# RPICM4.net
KiCad netlist of a schematic drawn in Altium Designer
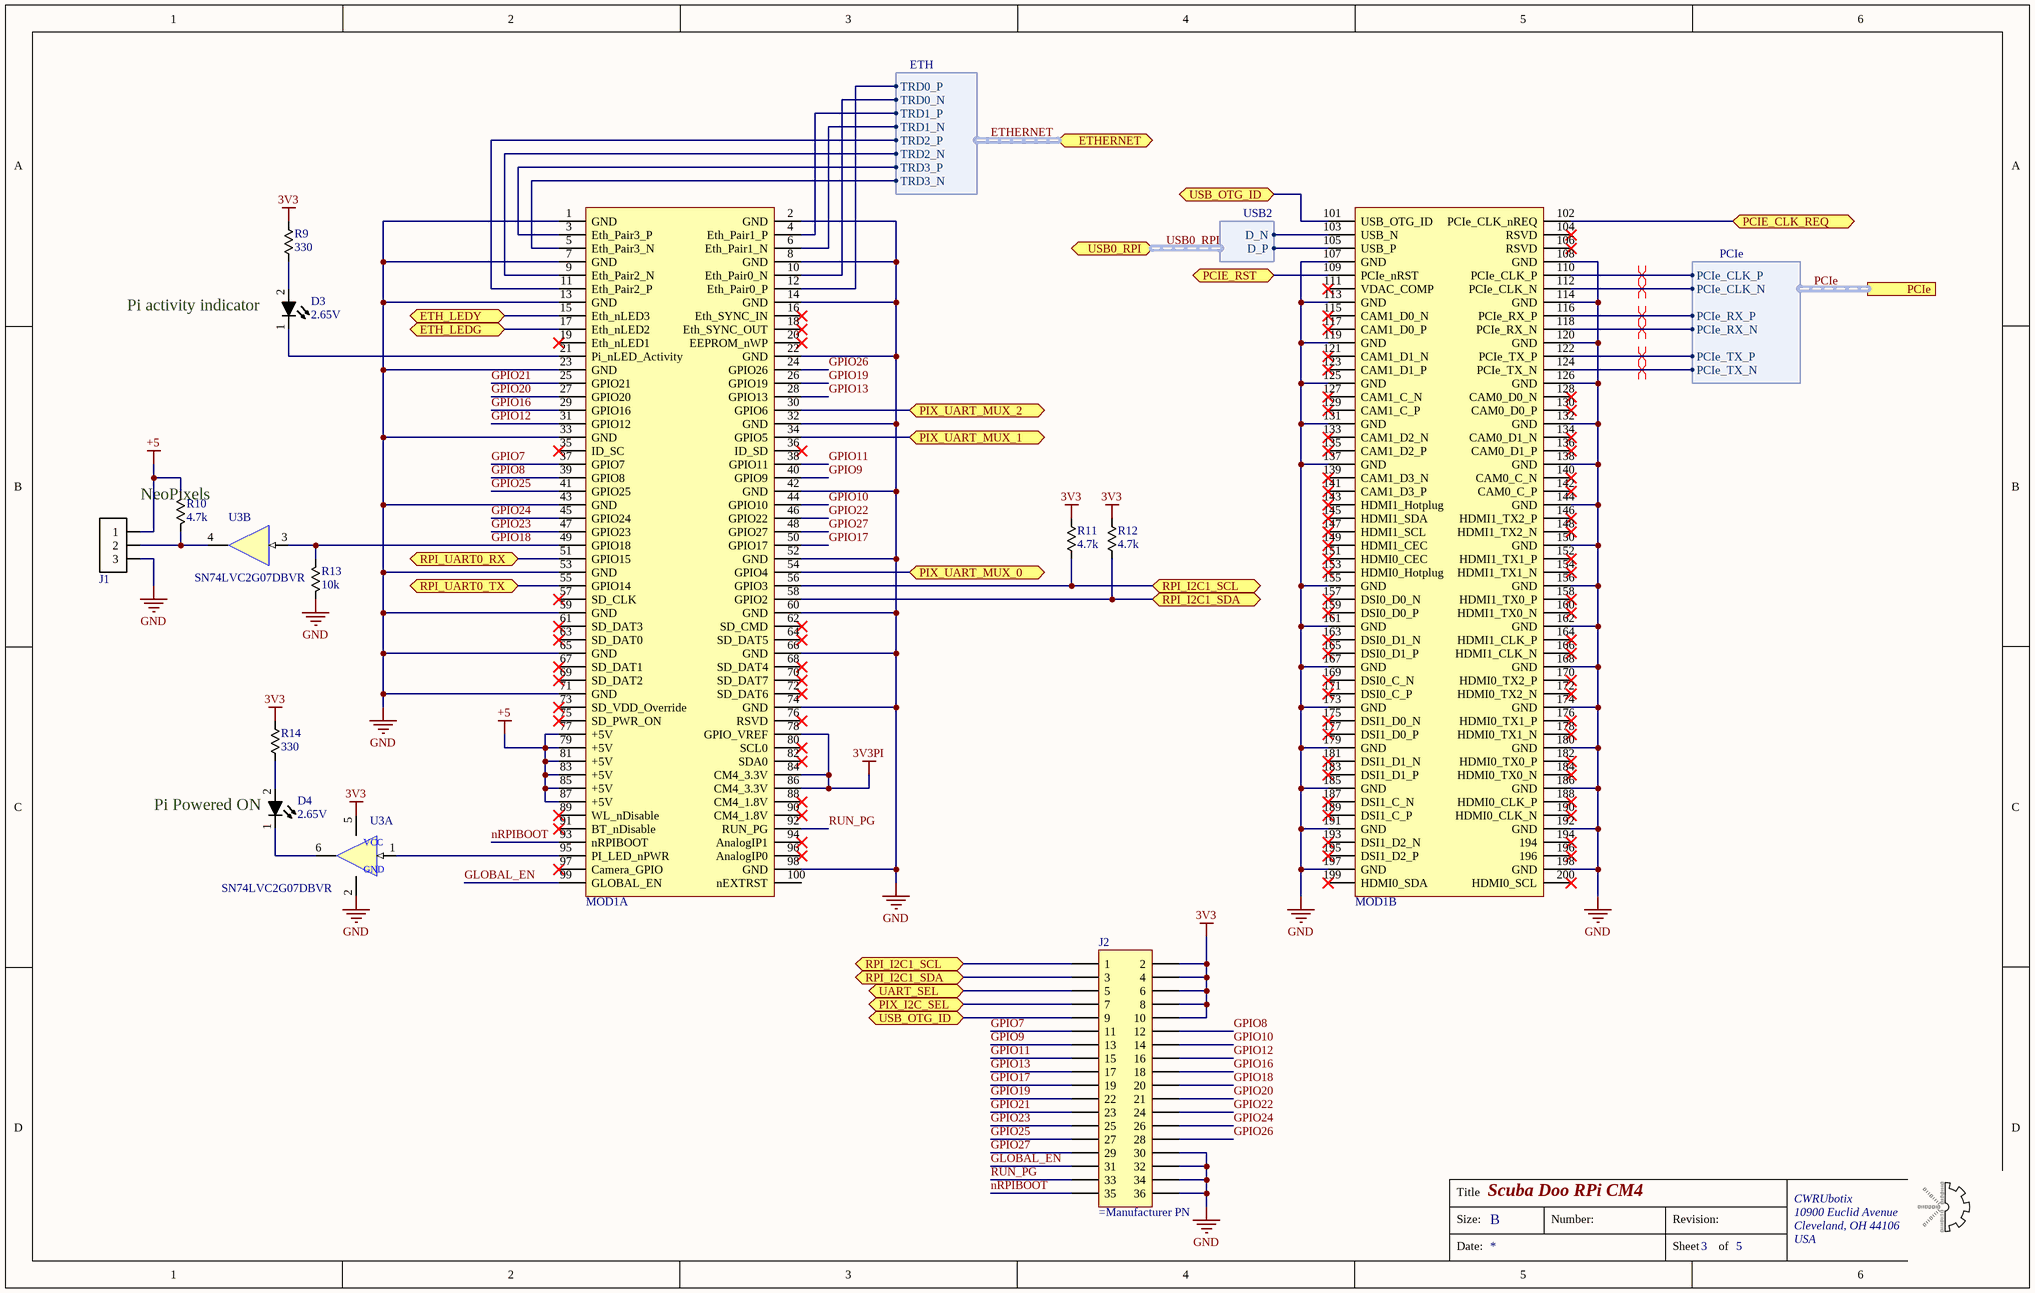
[diagram p0: RPICM4.SchDoc]

(export (version "E")
  (design (tool "Eeschema 10.0.6"))
  (components
    (comp (ref "D3")
      (value "2.65V")
      (footprint "chip_0603_LED")
      (description "LED, Green, 0603, Low current, HELI2 Series")
      (fields (field (name "PART NUMBER") "DIO-00050") (field (name "MANUFACTURER") "Kingbright"))
      (libsource (lib "Diodes$") (part "DIO-00050"))
    )
    (comp (ref "D4")
      (value "2.65V")
      (footprint "chip_0603_LED")
      (description "LED, Green, 0603, Low current, HELI2 Series")
      (fields (field (name "PART NUMBER") "DIO-00050") (field (name "MANUFACTURER") "Kingbright"))
      (libsource (lib "Diodes$") (part "DIO-00050"))
    )
    (comp (ref "J1")
      (value "conn-3x1_0")
      (footprint "HDDR_3x1_0")
      (description "Header, 3x1, 0.1\"")
      (fields (field (name "PART NUMBER") "CONN-00037"))
      (libsource (lib "Connectors$") (part "CONN-00037"))
    )
    (comp (ref "J2")
      (value "~")
      (footprint "HDDR_18X2_0")
      (description "Header 18x2, 0.1\"")
      (fields (field (name "PART NUMBER") "CONN-00005"))
      (libsource (lib "Connectors$") (part "CONN-00005"))
    )
    (comp (ref "MOD1")
      (value "CM4004032")
      (footprint "RPI_CM4_3MM")
      (description "Raspberry Pi 4 Compute Module, CM4, 4GB DDR4, 32 GB eMMC")
      (fields
        (field (name "PART NUMBER") "MISC-00060")
        (field (name "MANUFACTURER") "Raspberry Pi Foundation")
      )
      (libsource (lib "Misc$") (part "MISC-00060"))
    )
    (comp (ref "R9")
      (value "330")
      (footprint "chip_0603")
      (description "RES SMD 330 OHM 1% 1/4W 0603")
      (fields (field (name "PART NUMBER") "RES-00221") (field (name "TOLERANCE") "1%"))
      (libsource (lib "Resistors$") (part "RES-00221"))
    )
    (comp (ref "R10")
      (value "4.7k")
      (footprint "chip_0603")
      (description "RES SMD 4.7K OHM 1% 1/4W 0603")
      (fields (field (name "PART NUMBER") "RES-00470") (field (name "TOLERANCE") "1%"))
      (libsource (lib "Resistors$") (part "RES-00470"))
    )
    (comp (ref "R11")
      (value "4.7k")
      (footprint "chip_0603")
      (description "RES SMD 4.7K OHM 1% 1/4W 0603")
      (fields (field (name "PART NUMBER") "RES-00470") (field (name "TOLERANCE") "1%"))
      (libsource (lib "Resistors$") (part "RES-00470"))
    )
    (comp (ref "R12")
      (value "4.7k")
      (footprint "chip_0603")
      (description "RES SMD 4.7K OHM 1% 1/4W 0603")
      (fields (field (name "PART NUMBER") "RES-00470") (field (name "TOLERANCE") "1%"))
      (libsource (lib "Resistors$") (part "RES-00470"))
    )
    (comp (ref "R13")
      (value "10k")
      (footprint "chip_0603")
      (description "RES SMD 10K OHM 1% 1/4W 0603")
      (fields (field (name "PART NUMBER") "RES-00306") (field (name "TOLERANCE") "1%"))
      (libsource (lib "Resistors$") (part "RES-00306"))
    )
    (comp (ref "R14")
      (value "330")
      (footprint "chip_0603")
      (description "RES SMD 330 OHM 1% 1/4W 0603")
      (fields (field (name "PART NUMBER") "RES-00221") (field (name "TOLERANCE") "1%"))
      (libsource (lib "Resistors$") (part "RES-00221"))
    )
    (comp (ref "U3")
      (value "SN74LVC2G07DBVR")
      (footprint "sot-23-6")
      (description "IC, Buffer Non-Inverting, Dual, Open-Drain Outputs, 1.65~5.5V, SOT-23-6")
      (fields (field (name "PART NUMBER") "LOGIC-00046") (field (name "MANUFACTURER") "TI"))
      (libsource (lib "Logic$") (part "LOGIC-00046"))
    )
  )
  (nets
    (net (code "4") (name "+5") (class "Default")
      (node (ref "J1") (pin "1") (pinfunction "1_1") (pintype "passive"))
      (node (ref "MOD1") (pin "77") (pinfunction "+5V_77") (pintype "passive"))
      (node (ref "MOD1") (pin "79") (pinfunction "+5V_79") (pintype "passive"))
      (node (ref "MOD1") (pin "81") (pinfunction "+5V_81") (pintype "passive"))
      (node (ref "MOD1") (pin "83") (pinfunction "+5V_83") (pintype "passive"))
      (node (ref "MOD1") (pin "85") (pinfunction "+5V_85") (pintype "passive"))
      (node (ref "MOD1") (pin "87") (pinfunction "+5V_87") (pintype "passive"))
      (node (ref "R10") (pin "1") (pinfunction "1_1") (pintype "passive"))
    )
    (net (code "5") (name "/D_N") (class "Default")
      (node (ref "MOD1") (pin "103") (pinfunction "USB_N_103") (pintype "passive"))
    )
    (net (code "6") (name "/D_P") (class "Default")
      (node (ref "MOD1") (pin "105") (pinfunction "USB_P_105") (pintype "passive"))
    )
    (net (code "8") (name "/ETH_LEDG") (class "Default")
      (node (ref "MOD1") (pin "17") (pinfunction "Eth_nLED2_17") (pintype "passive"))
    )
    (net (code "9") (name "/ETH_LEDY") (class "Default")
      (node (ref "MOD1") (pin "15") (pinfunction "Eth_nLED3_15") (pintype "passive"))
    )
    (net (code "10") (name "/GLOBAL_EN") (class "Default")
      (node (ref "J2") (pin "31") (pinfunction "31_31") (pintype "passive"))
      (node (ref "MOD1") (pin "99") (pinfunction "GLOBAL_EN_99") (pintype "passive"))
    )
    (net (code "11") (name "/GPIO7") (class "Default")
      (node (ref "J2") (pin "11") (pinfunction "11_11") (pintype "passive"))
      (node (ref "MOD1") (pin "37") (pinfunction "GPIO7_37") (pintype "passive"))
    )
    (net (code "12") (name "/GPIO8") (class "Default")
      (node (ref "J2") (pin "12") (pinfunction "12_12") (pintype "passive"))
      (node (ref "MOD1") (pin "39") (pinfunction "GPIO8_39") (pintype "passive"))
    )
    (net (code "13") (name "/GPIO9") (class "Default")
      (node (ref "J2") (pin "13") (pinfunction "13_13") (pintype "passive"))
      (node (ref "MOD1") (pin "40") (pinfunction "GPIO9_40") (pintype "passive"))
    )
    (net (code "14") (name "/GPIO10") (class "Default")
      (node (ref "J2") (pin "14") (pinfunction "14_14") (pintype "passive"))
      (node (ref "MOD1") (pin "44") (pinfunction "GPIO10_44") (pintype "passive"))
    )
    (net (code "15") (name "/GPIO11") (class "Default")
      (node (ref "J2") (pin "15") (pinfunction "15_15") (pintype "passive"))
      (node (ref "MOD1") (pin "38") (pinfunction "GPIO11_38") (pintype "passive"))
    )
    (net (code "16") (name "/GPIO12") (class "Default")
      (node (ref "J2") (pin "16") (pinfunction "16_16") (pintype "passive"))
      (node (ref "MOD1") (pin "31") (pinfunction "GPIO12_31") (pintype "passive"))
    )
    (net (code "17") (name "/GPIO13") (class "Default")
      (node (ref "J2") (pin "17") (pinfunction "17_17") (pintype "passive"))
      (node (ref "MOD1") (pin "28") (pinfunction "GPIO13_28") (pintype "passive"))
    )
    (net (code "18") (name "/GPIO16") (class "Default")
      (node (ref "J2") (pin "18") (pinfunction "18_18") (pintype "passive"))
      (node (ref "MOD1") (pin "29") (pinfunction "GPIO16_29") (pintype "passive"))
    )
    (net (code "19") (name "/GPIO17") (class "Default")
      (node (ref "J2") (pin "19") (pinfunction "19_19") (pintype "passive"))
      (node (ref "MOD1") (pin "50") (pinfunction "GPIO17_50") (pintype "passive"))
    )
    (net (code "20") (name "/GPIO18") (class "Default")
      (node (ref "J2") (pin "20") (pinfunction "20_20") (pintype "passive"))
      (node (ref "MOD1") (pin "49") (pinfunction "GPIO18_49") (pintype "passive"))
      (node (ref "R13") (pin "1") (pinfunction "1_1") (pintype "passive"))
      (node (ref "U3") (pin "3") (pinfunction "2A_3") (pintype "input"))
    )
    (net (code "21") (name "/GPIO19") (class "Default")
      (node (ref "J2") (pin "22") (pinfunction "22_22") (pintype "passive"))
      (node (ref "MOD1") (pin "26") (pinfunction "GPIO19_26") (pintype "passive"))
    )
    (net (code "22") (name "/GPIO20") (class "Default")
      (node (ref "J2") (pin "21") (pinfunction "21_21") (pintype "passive"))
      (node (ref "MOD1") (pin "27") (pinfunction "GPIO20_27") (pintype "passive"))
    )
    (net (code "23") (name "/GPIO21") (class "Default")
      (node (ref "J2") (pin "23") (pinfunction "23_23") (pintype "passive"))
      (node (ref "MOD1") (pin "25") (pinfunction "GPIO21_25") (pintype "passive"))
    )
    (net (code "24") (name "/GPIO22") (class "Default")
      (node (ref "J2") (pin "24") (pinfunction "24_24") (pintype "passive"))
      (node (ref "MOD1") (pin "46") (pinfunction "GPIO22_46") (pintype "passive"))
    )
    (net (code "25") (name "/GPIO23") (class "Default")
      (node (ref "J2") (pin "25") (pinfunction "25_25") (pintype "passive"))
      (node (ref "MOD1") (pin "47") (pinfunction "GPIO23_47") (pintype "passive"))
    )
    (net (code "26") (name "/GPIO24") (class "Default")
      (node (ref "J2") (pin "26") (pinfunction "26_26") (pintype "passive"))
      (node (ref "MOD1") (pin "45") (pinfunction "GPIO24_45") (pintype "passive"))
    )
    (net (code "27") (name "/GPIO25") (class "Default")
      (node (ref "J2") (pin "27") (pinfunction "27_27") (pintype "passive"))
      (node (ref "MOD1") (pin "41") (pinfunction "GPIO25_41") (pintype "passive"))
    )
    (net (code "28") (name "/GPIO26") (class "Default")
      (node (ref "J2") (pin "28") (pinfunction "28_28") (pintype "passive"))
      (node (ref "MOD1") (pin "24") (pinfunction "GPIO26_24") (pintype "passive"))
    )
    (net (code "29") (name "/GPIO27") (class "Default")
      (node (ref "J2") (pin "29") (pinfunction "29_29") (pintype "passive"))
      (node (ref "MOD1") (pin "48") (pinfunction "GPIO27_48") (pintype "passive"))
    )
    (net (code "30") (name "/PCIE_CLK_REQ") (class "Default")
      (node (ref "MOD1") (pin "102") (pinfunction "PCIe_CLK_nREQ_102") (pintype "passive"))
    )
    (net (code "31") (name "/PCIE_RST") (class "Default")
      (node (ref "MOD1") (pin "109") (pinfunction "PCIe_nRST_109") (pintype "passive"))
    )
    (net (code "32") (name "/PCIe_CLK_N") (class "Default")
      (node (ref "MOD1") (pin "112") (pinfunction "PCIe_CLK_N_112") (pintype "passive"))
    )
    (net (code "33") (name "/PCIe_CLK_P") (class "Default")
      (node (ref "MOD1") (pin "110") (pinfunction "PCIe_CLK_P_110") (pintype "passive"))
    )
    (net (code "34") (name "/PCIe_RX_N") (class "Default")
      (node (ref "MOD1") (pin "118") (pinfunction "PCIe_RX_N_118") (pintype "passive"))
    )
    (net (code "35") (name "/PCIe_RX_P") (class "Default")
      (node (ref "MOD1") (pin "116") (pinfunction "PCIe_RX_P_116") (pintype "passive"))
    )
    (net (code "36") (name "/PCIe_TX_N") (class "Default")
      (node (ref "MOD1") (pin "124") (pinfunction "PCIe_TX_N_124") (pintype "passive"))
    )
    (net (code "37") (name "/PCIe_TX_P") (class "Default")
      (node (ref "MOD1") (pin "122") (pinfunction "PCIe_TX_P_122") (pintype "passive"))
    )
    (net (code "39") (name "/PIX_I2C_SEL") (class "Default")
      (node (ref "J2") (pin "7") (pinfunction "7_7") (pintype "passive"))
    )
    (net (code "40") (name "/PIX_UART_MUX_0") (class "Default")
      (node (ref "MOD1") (pin "54") (pinfunction "GPIO4_54") (pintype "passive"))
    )
    (net (code "41") (name "/PIX_UART_MUX_1") (class "Default")
      (node (ref "MOD1") (pin "34") (pinfunction "GPIO5_34") (pintype "passive"))
    )
    (net (code "42") (name "/PIX_UART_MUX_2") (class "Default")
      (node (ref "MOD1") (pin "30") (pinfunction "GPIO6_30") (pintype "passive"))
    )
    (net (code "43") (name "/RPI_I2C1_SCL") (class "Default")
      (node (ref "J2") (pin "1") (pinfunction "1_1") (pintype "passive"))
      (node (ref "MOD1") (pin "56") (pinfunction "GPIO3_56") (pintype "passive"))
      (node (ref "R11") (pin "2") (pinfunction "2_2") (pintype "passive"))
    )
    (net (code "44") (name "/RPI_I2C1_SDA") (class "Default")
      (node (ref "J2") (pin "3") (pinfunction "3_3") (pintype "passive"))
      (node (ref "MOD1") (pin "58") (pinfunction "GPIO2_58") (pintype "passive"))
      (node (ref "R12") (pin "2") (pinfunction "2_2") (pintype "passive"))
    )
    (net (code "45") (name "/RPI_UART0_RX") (class "Default")
      (node (ref "MOD1") (pin "51") (pinfunction "GPIO15_51") (pintype "passive"))
    )
    (net (code "46") (name "/RPI_UART0_TX") (class "Default")
      (node (ref "MOD1") (pin "55") (pinfunction "GPIO14_55") (pintype "passive"))
    )
    (net (code "47") (name "/RUN_PG") (class "Default")
      (node (ref "J2") (pin "33") (pinfunction "33_33") (pintype "passive"))
      (node (ref "MOD1") (pin "92") (pinfunction "RUN_PG_92") (pintype "passive"))
    )
    (net (code "48") (name "/TRD0_N") (class "Default")
      (node (ref "MOD1") (pin "10") (pinfunction "Eth_Pair0_N_10") (pintype "passive"))
    )
    (net (code "49") (name "/TRD0_P") (class "Default")
      (node (ref "MOD1") (pin "12") (pinfunction "Eth_Pair0_P_12") (pintype "passive"))
    )
    (net (code "50") (name "/TRD1_N") (class "Default")
      (node (ref "MOD1") (pin "6") (pinfunction "Eth_Pair1_N_6") (pintype "passive"))
    )
    (net (code "51") (name "/TRD1_P") (class "Default")
      (node (ref "MOD1") (pin "4") (pinfunction "Eth_Pair1_P_4") (pintype "passive"))
    )
    (net (code "52") (name "/TRD2_N") (class "Default")
      (node (ref "MOD1") (pin "9") (pinfunction "Eth_Pair2_N_9") (pintype "passive"))
    )
    (net (code "53") (name "/TRD2_P") (class "Default")
      (node (ref "MOD1") (pin "11") (pinfunction "Eth_Pair2_P_11") (pintype "passive"))
    )
    (net (code "54") (name "/TRD3_N") (class "Default")
      (node (ref "MOD1") (pin "5") (pinfunction "Eth_Pair3_N_5") (pintype "passive"))
    )
    (net (code "55") (name "/TRD3_P") (class "Default")
      (node (ref "MOD1") (pin "3") (pinfunction "Eth_Pair3_P_3") (pintype "passive"))
    )
    (net (code "56") (name "/UART_SEL") (class "Default")
      (node (ref "J2") (pin "5") (pinfunction "5_5") (pintype "passive"))
    )
    (net (code "58") (name "/USB_OTG_ID") (class "Default")
      (node (ref "J2") (pin "9") (pinfunction "9_9") (pintype "passive"))
      (node (ref "MOD1") (pin "101") (pinfunction "USB_OTG_ID_101") (pintype "passive"))
    )
    (net (code "59") (name "/nRPIBOOT") (class "Default")
      (node (ref "J2") (pin "35") (pinfunction "35_35") (pintype "passive"))
      (node (ref "MOD1") (pin "93") (pinfunction "nRPIBOOT_93") (pintype "passive"))
    )
    (net (code "60") (name "3V3") (class "Default")
      (node (ref "J2") (pin "10") (pinfunction "10_10") (pintype "passive"))
      (node (ref "J2") (pin "2") (pinfunction "2_2") (pintype "passive"))
      (node (ref "J2") (pin "4") (pinfunction "4_4") (pintype "passive"))
      (node (ref "J2") (pin "6") (pinfunction "6_6") (pintype "passive"))
      (node (ref "J2") (pin "8") (pinfunction "8_8") (pintype "passive"))
      (node (ref "R11") (pin "1") (pinfunction "1_1") (pintype "passive"))
      (node (ref "R12") (pin "1") (pinfunction "1_1") (pintype "passive"))
      (node (ref "R14") (pin "1") (pinfunction "1_1") (pintype "passive"))
      (node (ref "R9") (pin "1") (pinfunction "1_1") (pintype "passive"))
      (node (ref "U3") (pin "5") (pinfunction "VCC_5") (pintype "power_in"))
    )
    (net (code "61") (name "3V3PI") (class "Default")
      (node (ref "MOD1") (pin "78") (pinfunction "GPIO_VREF_78") (pintype "passive"))
      (node (ref "MOD1") (pin "84") (pinfunction "CM4_3.3V_84") (pintype "passive"))
      (node (ref "MOD1") (pin "86") (pinfunction "CM4_3.3V_86") (pintype "passive"))
    )
    (net (code "62") (name "GND") (class "Default")
      (node (ref "J1") (pin "3") (pinfunction "3_3") (pintype "passive"))
      (node (ref "J2") (pin "30") (pinfunction "30_30") (pintype "passive"))
      (node (ref "J2") (pin "32") (pinfunction "32_32") (pintype "passive"))
      (node (ref "J2") (pin "34") (pinfunction "34_34") (pintype "passive"))
      (node (ref "J2") (pin "36") (pinfunction "36_36") (pintype "passive"))
      (node (ref "MOD1") (pin "1") (pinfunction "GND_1") (pintype "passive"))
      (node (ref "MOD1") (pin "107") (pinfunction "GND_107") (pintype "passive"))
      (node (ref "MOD1") (pin "108") (pinfunction "GND_108") (pintype "passive"))
      (node (ref "MOD1") (pin "113") (pinfunction "GND_113") (pintype "passive"))
      (node (ref "MOD1") (pin "114") (pinfunction "GND_114") (pintype "passive"))
      (node (ref "MOD1") (pin "119") (pinfunction "GND_119") (pintype "passive"))
      (node (ref "MOD1") (pin "120") (pinfunction "GND_120") (pintype "passive"))
      (node (ref "MOD1") (pin "125") (pinfunction "GND_125") (pintype "passive"))
      (node (ref "MOD1") (pin "126") (pinfunction "GND_126") (pintype "passive"))
      (node (ref "MOD1") (pin "13") (pinfunction "GND_13") (pintype "passive"))
      (node (ref "MOD1") (pin "131") (pinfunction "GND_131") (pintype "passive"))
      (node (ref "MOD1") (pin "132") (pinfunction "GND_132") (pintype "passive"))
      (node (ref "MOD1") (pin "137") (pinfunction "GND_137") (pintype "passive"))
      (node (ref "MOD1") (pin "138") (pinfunction "GND_138") (pintype "passive"))
      (node (ref "MOD1") (pin "14") (pinfunction "GND_14") (pintype "passive"))
      (node (ref "MOD1") (pin "144") (pinfunction "GND_144") (pintype "passive"))
      (node (ref "MOD1") (pin "150") (pinfunction "GND_150") (pintype "passive"))
      (node (ref "MOD1") (pin "155") (pinfunction "GND_155") (pintype "passive"))
      (node (ref "MOD1") (pin "156") (pinfunction "GND_156") (pintype "passive"))
      (node (ref "MOD1") (pin "161") (pinfunction "GND_161") (pintype "passive"))
      (node (ref "MOD1") (pin "162") (pinfunction "GND_162") (pintype "passive"))
      (node (ref "MOD1") (pin "167") (pinfunction "GND_167") (pintype "passive"))
      (node (ref "MOD1") (pin "168") (pinfunction "GND_168") (pintype "passive"))
      (node (ref "MOD1") (pin "173") (pinfunction "GND_173") (pintype "passive"))
      (node (ref "MOD1") (pin "174") (pinfunction "GND_174") (pintype "passive"))
      (node (ref "MOD1") (pin "179") (pinfunction "GND_179") (pintype "passive"))
      (node (ref "MOD1") (pin "180") (pinfunction "GND_180") (pintype "passive"))
      (node (ref "MOD1") (pin "185") (pinfunction "GND_185") (pintype "passive"))
      (node (ref "MOD1") (pin "186") (pinfunction "GND_186") (pintype "passive"))
      (node (ref "MOD1") (pin "191") (pinfunction "GND_191") (pintype "passive"))
      (node (ref "MOD1") (pin "192") (pinfunction "GND_192") (pintype "passive"))
      (node (ref "MOD1") (pin "197") (pinfunction "GND_197") (pintype "passive"))
      (node (ref "MOD1") (pin "198") (pinfunction "GND_198") (pintype "passive"))
      (node (ref "MOD1") (pin "2") (pinfunction "GND_2") (pintype "passive"))
      (node (ref "MOD1") (pin "22") (pinfunction "GND_22") (pintype "passive"))
      (node (ref "MOD1") (pin "23") (pinfunction "GND_23") (pintype "passive"))
      (node (ref "MOD1") (pin "32") (pinfunction "GND_32") (pintype "passive"))
      (node (ref "MOD1") (pin "33") (pinfunction "GND_33") (pintype "passive"))
      (node (ref "MOD1") (pin "42") (pinfunction "GND_42") (pintype "passive"))
      (node (ref "MOD1") (pin "43") (pinfunction "GND_43") (pintype "passive"))
      (node (ref "MOD1") (pin "52") (pinfunction "GND_52") (pintype "passive"))
      (node (ref "MOD1") (pin "53") (pinfunction "GND_53") (pintype "passive"))
      (node (ref "MOD1") (pin "59") (pinfunction "GND_59") (pintype "passive"))
      (node (ref "MOD1") (pin "60") (pinfunction "GND_60") (pintype "passive"))
      (node (ref "MOD1") (pin "65") (pinfunction "GND_65") (pintype "passive"))
      (node (ref "MOD1") (pin "66") (pinfunction "GND_66") (pintype "passive"))
      (node (ref "MOD1") (pin "7") (pinfunction "GND_7") (pintype "passive"))
      (node (ref "MOD1") (pin "71") (pinfunction "GND_71") (pintype "passive"))
      (node (ref "MOD1") (pin "74") (pinfunction "GND_74") (pintype "passive"))
      (node (ref "MOD1") (pin "8") (pinfunction "GND_8") (pintype "passive"))
      (node (ref "MOD1") (pin "98") (pinfunction "GND_98") (pintype "passive"))
      (node (ref "R13") (pin "2") (pinfunction "2_2") (pintype "passive"))
      (node (ref "U3") (pin "2") (pinfunction "GND_2") (pintype "power_in"))
    )
    (net (code "63") (name "Net-(D3-Pad2)") (class "Default")
      (node (ref "D3") (pin "2") (pinfunction "2_2") (pintype "passive"))
      (node (ref "R9") (pin "2") (pinfunction "2_2") (pintype "passive"))
    )
    (net (code "64") (name "Net-(D4-Pad2)") (class "Default")
      (node (ref "D4") (pin "2") (pinfunction "2_2") (pintype "passive"))
      (node (ref "R14") (pin "2") (pinfunction "2_2") (pintype "passive"))
    )
    (net (code "65") (name "Net-(MOD1A-PI_LED_nPWR)") (class "Default")
      (node (ref "MOD1") (pin "95") (pinfunction "PI_LED_nPWR_95") (pintype "passive"))
      (node (ref "U3") (pin "1") (pinfunction "1A_1") (pintype "input"))
    )
    (net (code "66") (name "Net-(MOD1A-Pi_nLED_Activity)") (class "Default")
      (node (ref "D3") (pin "1") (pinfunction "1_1") (pintype "passive"))
      (node (ref "MOD1") (pin "21") (pinfunction "Pi_nLED_Activity_21") (pintype "passive"))
    )
    (net (code "67") (name "Net-(U3A-1Y)") (class "Default")
      (node (ref "D4") (pin "1") (pinfunction "1_1") (pintype "passive"))
      (node (ref "U3") (pin "6") (pinfunction "1Y_6") (pintype "open_collector"))
    )
    (net (code "68") (name "Net-(U3B-2Y)") (class "Default")
      (node (ref "J1") (pin "2") (pinfunction "2_2") (pintype "passive"))
      (node (ref "R10") (pin "2") (pinfunction "2_2") (pintype "passive"))
      (node (ref "U3") (pin "4") (pinfunction "2Y_4") (pintype "open_collector"))
    )
    (net (code "69") (name "unconnected-(MOD1-Pad194)") (class "Default")
      (node (ref "MOD1") (pin "194") (pinfunction "194_194") (pintype "passive+no_connect"))
    )
    (net (code "70") (name "unconnected-(MOD1-Pad196)") (class "Default")
      (node (ref "MOD1") (pin "196") (pinfunction "196_196") (pintype "passive+no_connect"))
    )
    (net (code "71") (name "unconnected-(MOD1A-AnalogIP0-Pad96)") (class "Default")
      (node (ref "MOD1") (pin "96") (pinfunction "AnalogIP0_96") (pintype "passive+no_connect"))
    )
    (net (code "72") (name "unconnected-(MOD1A-AnalogIP1-Pad94)") (class "Default")
      (node (ref "MOD1") (pin "94") (pinfunction "AnalogIP1_94") (pintype "passive+no_connect"))
    )
    (net (code "73") (name "unconnected-(MOD1A-BT_nDisable-Pad91)") (class "Default")
      (node (ref "MOD1") (pin "91") (pinfunction "BT_nDisable_91") (pintype "passive+no_connect"))
    )
    (net (code "74") (name "unconnected-(MOD1A-CM4_1.8V-Pad88)") (class "Default")
      (node (ref "MOD1") (pin "88") (pinfunction "CM4_1.8V_88") (pintype "passive+no_connect"))
    )
    (net (code "75") (name "unconnected-(MOD1A-CM4_1.8V-Pad90)") (class "Default")
      (node (ref "MOD1") (pin "90") (pinfunction "CM4_1.8V_90") (pintype "passive+no_connect"))
    )
    (net (code "76") (name "unconnected-(MOD1A-Camera_GPIO-Pad97)") (class "Default")
      (node (ref "MOD1") (pin "97") (pinfunction "Camera_GPIO_97") (pintype "passive+no_connect"))
    )
    (net (code "77") (name "unconnected-(MOD1A-EEPROM_nWP-Pad20)") (class "Default")
      (node (ref "MOD1") (pin "20") (pinfunction "EEPROM_nWP_20") (pintype "passive+no_connect"))
    )
    (net (code "78") (name "unconnected-(MOD1A-Eth_SYNC_IN-Pad16)") (class "Default")
      (node (ref "MOD1") (pin "16") (pinfunction "Eth_SYNC_IN_16") (pintype "passive+no_connect"))
    )
    (net (code "79") (name "unconnected-(MOD1A-Eth_SYNC_OUT-Pad18)") (class "Default")
      (node (ref "MOD1") (pin "18") (pinfunction "Eth_SYNC_OUT_18") (pintype "passive+no_connect"))
    )
    (net (code "80") (name "unconnected-(MOD1A-Eth_nLED1-Pad19)") (class "Default")
      (node (ref "MOD1") (pin "19") (pinfunction "Eth_nLED1_19") (pintype "passive+no_connect"))
    )
    (net (code "81") (name "unconnected-(MOD1A-ID_SC-Pad35)") (class "Default")
      (node (ref "MOD1") (pin "35") (pinfunction "ID_SC_35") (pintype "passive+no_connect"))
    )
    (net (code "82") (name "unconnected-(MOD1A-ID_SD-Pad36)") (class "Default")
      (node (ref "MOD1") (pin "36") (pinfunction "ID_SD_36") (pintype "passive+no_connect"))
    )
    (net (code "83") (name "unconnected-(MOD1A-RSVD-Pad76)") (class "Default")
      (node (ref "MOD1") (pin "76") (pinfunction "RSVD_76") (pintype "passive+no_connect"))
    )
    (net (code "84") (name "unconnected-(MOD1A-SCL0-Pad80)") (class "Default")
      (node (ref "MOD1") (pin "80") (pinfunction "SCL0_80") (pintype "passive+no_connect"))
    )
    (net (code "85") (name "unconnected-(MOD1A-SDA0-Pad82)") (class "Default")
      (node (ref "MOD1") (pin "82") (pinfunction "SDA0_82") (pintype "passive+no_connect"))
    )
    (net (code "86") (name "unconnected-(MOD1A-SD_CLK-Pad57)") (class "Default")
      (node (ref "MOD1") (pin "57") (pinfunction "SD_CLK_57") (pintype "passive+no_connect"))
    )
    (net (code "87") (name "unconnected-(MOD1A-SD_CMD-Pad62)") (class "Default")
      (node (ref "MOD1") (pin "62") (pinfunction "SD_CMD_62") (pintype "passive+no_connect"))
    )
    (net (code "88") (name "unconnected-(MOD1A-SD_DAT0-Pad63)") (class "Default")
      (node (ref "MOD1") (pin "63") (pinfunction "SD_DAT0_63") (pintype "passive+no_connect"))
    )
    (net (code "89") (name "unconnected-(MOD1A-SD_DAT1-Pad67)") (class "Default")
      (node (ref "MOD1") (pin "67") (pinfunction "SD_DAT1_67") (pintype "passive+no_connect"))
    )
    (net (code "90") (name "unconnected-(MOD1A-SD_DAT2-Pad69)") (class "Default")
      (node (ref "MOD1") (pin "69") (pinfunction "SD_DAT2_69") (pintype "passive+no_connect"))
    )
    (net (code "91") (name "unconnected-(MOD1A-SD_DAT3-Pad61)") (class "Default")
      (node (ref "MOD1") (pin "61") (pinfunction "SD_DAT3_61") (pintype "passive+no_connect"))
    )
    (net (code "92") (name "unconnected-(MOD1A-SD_DAT4-Pad68)") (class "Default")
      (node (ref "MOD1") (pin "68") (pinfunction "SD_DAT4_68") (pintype "passive+no_connect"))
    )
    (net (code "93") (name "unconnected-(MOD1A-SD_DAT5-Pad64)") (class "Default")
      (node (ref "MOD1") (pin "64") (pinfunction "SD_DAT5_64") (pintype "passive+no_connect"))
    )
    (net (code "94") (name "unconnected-(MOD1A-SD_DAT6-Pad72)") (class "Default")
      (node (ref "MOD1") (pin "72") (pinfunction "SD_DAT6_72") (pintype "passive+no_connect"))
    )
    (net (code "95") (name "unconnected-(MOD1A-SD_DAT7-Pad70)") (class "Default")
      (node (ref "MOD1") (pin "70") (pinfunction "SD_DAT7_70") (pintype "passive+no_connect"))
    )
    (net (code "96") (name "unconnected-(MOD1A-SD_PWR_ON-Pad75)") (class "Default")
      (node (ref "MOD1") (pin "75") (pinfunction "SD_PWR_ON_75") (pintype "passive+no_connect"))
    )
    (net (code "97") (name "unconnected-(MOD1A-SD_VDD_Override-Pad73)") (class "Default")
      (node (ref "MOD1") (pin "73") (pinfunction "SD_VDD_Override_73") (pintype "passive+no_connect"))
    )
    (net (code "98") (name "unconnected-(MOD1A-WL_nDisable-Pad89)") (class "Default")
      (node (ref "MOD1") (pin "89") (pinfunction "WL_nDisable_89") (pintype "passive+no_connect"))
    )
    (net (code "99") (name "unconnected-(MOD1A-nEXTRST-Pad100)") (class "Default")
      (node (ref "MOD1") (pin "100") (pinfunction "nEXTRST_100") (pintype "passive"))
    )
    (net (code "100") (name "unconnected-(MOD1B-CAM0_C_N-Pad140)") (class "Default")
      (node (ref "MOD1") (pin "140") (pinfunction "CAM0_C_N_140") (pintype "passive+no_connect"))
    )
    (net (code "101") (name "unconnected-(MOD1B-CAM0_C_P-Pad142)") (class "Default")
      (node (ref "MOD1") (pin "142") (pinfunction "CAM0_C_P_142") (pintype "passive+no_connect"))
    )
    (net (code "102") (name "unconnected-(MOD1B-CAM0_D0_N-Pad128)") (class "Default")
      (node (ref "MOD1") (pin "128") (pinfunction "CAM0_D0_N_128") (pintype "passive+no_connect"))
    )
    (net (code "103") (name "unconnected-(MOD1B-CAM0_D0_P-Pad130)") (class "Default")
      (node (ref "MOD1") (pin "130") (pinfunction "CAM0_D0_P_130") (pintype "passive+no_connect"))
    )
    (net (code "104") (name "unconnected-(MOD1B-CAM0_D1_N-Pad134)") (class "Default")
      (node (ref "MOD1") (pin "134") (pinfunction "CAM0_D1_N_134") (pintype "passive+no_connect"))
    )
    (net (code "105") (name "unconnected-(MOD1B-CAM0_D1_P-Pad136)") (class "Default")
      (node (ref "MOD1") (pin "136") (pinfunction "CAM0_D1_P_136") (pintype "passive+no_connect"))
    )
    (net (code "106") (name "unconnected-(MOD1B-CAM1_C_N-Pad127)") (class "Default")
      (node (ref "MOD1") (pin "127") (pinfunction "CAM1_C_N_127") (pintype "passive+no_connect"))
    )
    (net (code "107") (name "unconnected-(MOD1B-CAM1_C_P-Pad129)") (class "Default")
      (node (ref "MOD1") (pin "129") (pinfunction "CAM1_C_P_129") (pintype "passive+no_connect"))
    )
    (net (code "108") (name "unconnected-(MOD1B-CAM1_D0_N-Pad115)") (class "Default")
      (node (ref "MOD1") (pin "115") (pinfunction "CAM1_D0_N_115") (pintype "passive+no_connect"))
    )
    (net (code "109") (name "unconnected-(MOD1B-CAM1_D0_P-Pad117)") (class "Default")
      (node (ref "MOD1") (pin "117") (pinfunction "CAM1_D0_P_117") (pintype "passive+no_connect"))
    )
    (net (code "110") (name "unconnected-(MOD1B-CAM1_D1_N-Pad121)") (class "Default")
      (node (ref "MOD1") (pin "121") (pinfunction "CAM1_D1_N_121") (pintype "passive+no_connect"))
    )
    (net (code "111") (name "unconnected-(MOD1B-CAM1_D1_P-Pad123)") (class "Default")
      (node (ref "MOD1") (pin "123") (pinfunction "CAM1_D1_P_123") (pintype "passive+no_connect"))
    )
    (net (code "112") (name "unconnected-(MOD1B-CAM1_D2_N-Pad133)") (class "Default")
      (node (ref "MOD1") (pin "133") (pinfunction "CAM1_D2_N_133") (pintype "passive+no_connect"))
    )
    (net (code "113") (name "unconnected-(MOD1B-CAM1_D2_P-Pad135)") (class "Default")
      (node (ref "MOD1") (pin "135") (pinfunction "CAM1_D2_P_135") (pintype "passive+no_connect"))
    )
    (net (code "114") (name "unconnected-(MOD1B-CAM1_D3_N-Pad139)") (class "Default")
      (node (ref "MOD1") (pin "139") (pinfunction "CAM1_D3_N_139") (pintype "passive+no_connect"))
    )
    (net (code "115") (name "unconnected-(MOD1B-CAM1_D3_P-Pad141)") (class "Default")
      (node (ref "MOD1") (pin "141") (pinfunction "CAM1_D3_P_141") (pintype "passive+no_connect"))
    )
    (net (code "116") (name "unconnected-(MOD1B-DSI0_C_N-Pad169)") (class "Default")
      (node (ref "MOD1") (pin "169") (pinfunction "DSI0_C_N_169") (pintype "passive+no_connect"))
    )
    (net (code "117") (name "unconnected-(MOD1B-DSI0_C_P-Pad171)") (class "Default")
      (node (ref "MOD1") (pin "171") (pinfunction "DSI0_C_P_171") (pintype "passive+no_connect"))
    )
    (net (code "118") (name "unconnected-(MOD1B-DSI0_D0_N-Pad157)") (class "Default")
      (node (ref "MOD1") (pin "157") (pinfunction "DSI0_D0_N_157") (pintype "passive+no_connect"))
    )
    (net (code "119") (name "unconnected-(MOD1B-DSI0_D0_P-Pad159)") (class "Default")
      (node (ref "MOD1") (pin "159") (pinfunction "DSI0_D0_P_159") (pintype "passive+no_connect"))
    )
    (net (code "120") (name "unconnected-(MOD1B-DSI0_D1_N-Pad163)") (class "Default")
      (node (ref "MOD1") (pin "163") (pinfunction "DSI0_D1_N_163") (pintype "passive+no_connect"))
    )
    (net (code "121") (name "unconnected-(MOD1B-DSI0_D1_P-Pad165)") (class "Default")
      (node (ref "MOD1") (pin "165") (pinfunction "DSI0_D1_P_165") (pintype "passive+no_connect"))
    )
    (net (code "122") (name "unconnected-(MOD1B-DSI1_C_N-Pad187)") (class "Default")
      (node (ref "MOD1") (pin "187") (pinfunction "DSI1_C_N_187") (pintype "passive+no_connect"))
    )
    (net (code "123") (name "unconnected-(MOD1B-DSI1_C_P-Pad189)") (class "Default")
      (node (ref "MOD1") (pin "189") (pinfunction "DSI1_C_P_189") (pintype "passive+no_connect"))
    )
    (net (code "124") (name "unconnected-(MOD1B-DSI1_D0_N-Pad175)") (class "Default")
      (node (ref "MOD1") (pin "175") (pinfunction "DSI1_D0_N_175") (pintype "passive+no_connect"))
    )
    (net (code "125") (name "unconnected-(MOD1B-DSI1_D0_P-Pad177)") (class "Default")
      (node (ref "MOD1") (pin "177") (pinfunction "DSI1_D0_P_177") (pintype "passive+no_connect"))
    )
    (net (code "126") (name "unconnected-(MOD1B-DSI1_D1_N-Pad181)") (class "Default")
      (node (ref "MOD1") (pin "181") (pinfunction "DSI1_D1_N_181") (pintype "passive+no_connect"))
    )
    (net (code "127") (name "unconnected-(MOD1B-DSI1_D1_P-Pad183)") (class "Default")
      (node (ref "MOD1") (pin "183") (pinfunction "DSI1_D1_P_183") (pintype "passive+no_connect"))
    )
    (net (code "128") (name "unconnected-(MOD1B-DSI1_D2_N-Pad193)") (class "Default")
      (node (ref "MOD1") (pin "193") (pinfunction "DSI1_D2_N_193") (pintype "passive+no_connect"))
    )
    (net (code "129") (name "unconnected-(MOD1B-DSI1_D2_P-Pad195)") (class "Default")
      (node (ref "MOD1") (pin "195") (pinfunction "DSI1_D2_P_195") (pintype "passive+no_connect"))
    )
    (net (code "130") (name "unconnected-(MOD1B-HDMI0_CEC-Pad151)") (class "Default")
      (node (ref "MOD1") (pin "151") (pinfunction "HDMI0_CEC_151") (pintype "passive+no_connect"))
    )
    (net (code "131") (name "unconnected-(MOD1B-HDMI0_CLK_N-Pad190)") (class "Default")
      (node (ref "MOD1") (pin "190") (pinfunction "HDMI0_CLK_N_190") (pintype "passive+no_connect"))
    )
    (net (code "132") (name "unconnected-(MOD1B-HDMI0_CLK_P-Pad188)") (class "Default")
      (node (ref "MOD1") (pin "188") (pinfunction "HDMI0_CLK_P_188") (pintype "passive+no_connect"))
    )
    (net (code "133") (name "unconnected-(MOD1B-HDMI0_Hotplug-Pad153)") (class "Default")
      (node (ref "MOD1") (pin "153") (pinfunction "HDMI0_Hotplug_153") (pintype "passive+no_connect"))
    )
    (net (code "134") (name "unconnected-(MOD1B-HDMI0_SCL-Pad200)") (class "Default")
      (node (ref "MOD1") (pin "200") (pinfunction "HDMI0_SCL_200") (pintype "passive+no_connect"))
    )
    (net (code "135") (name "unconnected-(MOD1B-HDMI0_SDA-Pad199)") (class "Default")
      (node (ref "MOD1") (pin "199") (pinfunction "HDMI0_SDA_199") (pintype "passive+no_connect"))
    )
    (net (code "136") (name "unconnected-(MOD1B-HDMI0_TX0_N-Pad184)") (class "Default")
      (node (ref "MOD1") (pin "184") (pinfunction "HDMI0_TX0_N_184") (pintype "passive+no_connect"))
    )
    (net (code "137") (name "unconnected-(MOD1B-HDMI0_TX0_P-Pad182)") (class "Default")
      (node (ref "MOD1") (pin "182") (pinfunction "HDMI0_TX0_P_182") (pintype "passive+no_connect"))
    )
    (net (code "138") (name "unconnected-(MOD1B-HDMI0_TX1_N-Pad178)") (class "Default")
      (node (ref "MOD1") (pin "178") (pinfunction "HDMI0_TX1_N_178") (pintype "passive+no_connect"))
    )
    (net (code "139") (name "unconnected-(MOD1B-HDMI0_TX1_P-Pad176)") (class "Default")
      (node (ref "MOD1") (pin "176") (pinfunction "HDMI0_TX1_P_176") (pintype "passive+no_connect"))
    )
    (net (code "140") (name "unconnected-(MOD1B-HDMI0_TX2_N-Pad172)") (class "Default")
      (node (ref "MOD1") (pin "172") (pinfunction "HDMI0_TX2_N_172") (pintype "passive+no_connect"))
    )
    (net (code "141") (name "unconnected-(MOD1B-HDMI0_TX2_P-Pad170)") (class "Default")
      (node (ref "MOD1") (pin "170") (pinfunction "HDMI0_TX2_P_170") (pintype "passive+no_connect"))
    )
    (net (code "142") (name "unconnected-(MOD1B-HDMI1_CEC-Pad149)") (class "Default")
      (node (ref "MOD1") (pin "149") (pinfunction "HDMI1_CEC_149") (pintype "passive+no_connect"))
    )
    (net (code "143") (name "unconnected-(MOD1B-HDMI1_CLK_N-Pad166)") (class "Default")
      (node (ref "MOD1") (pin "166") (pinfunction "HDMI1_CLK_N_166") (pintype "passive+no_connect"))
    )
    (net (code "144") (name "unconnected-(MOD1B-HDMI1_CLK_P-Pad164)") (class "Default")
      (node (ref "MOD1") (pin "164") (pinfunction "HDMI1_CLK_P_164") (pintype "passive+no_connect"))
    )
    (net (code "145") (name "unconnected-(MOD1B-HDMI1_Hotplug-Pad143)") (class "Default")
      (node (ref "MOD1") (pin "143") (pinfunction "HDMI1_Hotplug_143") (pintype "passive+no_connect"))
    )
    (net (code "146") (name "unconnected-(MOD1B-HDMI1_SCL-Pad147)") (class "Default")
      (node (ref "MOD1") (pin "147") (pinfunction "HDMI1_SCL_147") (pintype "passive+no_connect"))
    )
    (net (code "147") (name "unconnected-(MOD1B-HDMI1_SDA-Pad145)") (class "Default")
      (node (ref "MOD1") (pin "145") (pinfunction "HDMI1_SDA_145") (pintype "passive+no_connect"))
    )
    (net (code "148") (name "unconnected-(MOD1B-HDMI1_TX0_N-Pad160)") (class "Default")
      (node (ref "MOD1") (pin "160") (pinfunction "HDMI1_TX0_N_160") (pintype "passive+no_connect"))
    )
    (net (code "149") (name "unconnected-(MOD1B-HDMI1_TX0_P-Pad158)") (class "Default")
      (node (ref "MOD1") (pin "158") (pinfunction "HDMI1_TX0_P_158") (pintype "passive+no_connect"))
    )
    (net (code "150") (name "unconnected-(MOD1B-HDMI1_TX1_N-Pad154)") (class "Default")
      (node (ref "MOD1") (pin "154") (pinfunction "HDMI1_TX1_N_154") (pintype "passive+no_connect"))
    )
    (net (code "151") (name "unconnected-(MOD1B-HDMI1_TX1_P-Pad152)") (class "Default")
      (node (ref "MOD1") (pin "152") (pinfunction "HDMI1_TX1_P_152") (pintype "passive+no_connect"))
    )
    (net (code "152") (name "unconnected-(MOD1B-HDMI1_TX2_N-Pad148)") (class "Default")
      (node (ref "MOD1") (pin "148") (pinfunction "HDMI1_TX2_N_148") (pintype "passive+no_connect"))
    )
    (net (code "153") (name "unconnected-(MOD1B-HDMI1_TX2_P-Pad146)") (class "Default")
      (node (ref "MOD1") (pin "146") (pinfunction "HDMI1_TX2_P_146") (pintype "passive+no_connect"))
    )
    (net (code "154") (name "unconnected-(MOD1B-RSVD-Pad104)") (class "Default")
      (node (ref "MOD1") (pin "104") (pinfunction "RSVD_104") (pintype "passive+no_connect"))
    )
    (net (code "155") (name "unconnected-(MOD1B-RSVD-Pad106)") (class "Default")
      (node (ref "MOD1") (pin "106") (pinfunction "RSVD_106") (pintype "passive+no_connect"))
    )
    (net (code "156") (name "unconnected-(MOD1B-VDAC_COMP-Pad111)") (class "Default")
      (node (ref "MOD1") (pin "111") (pinfunction "VDAC_COMP_111") (pintype "passive+no_connect"))
    )
  )
)
